# Actuator.net
KiCad netlist of a schematic drawn in Altium Designer
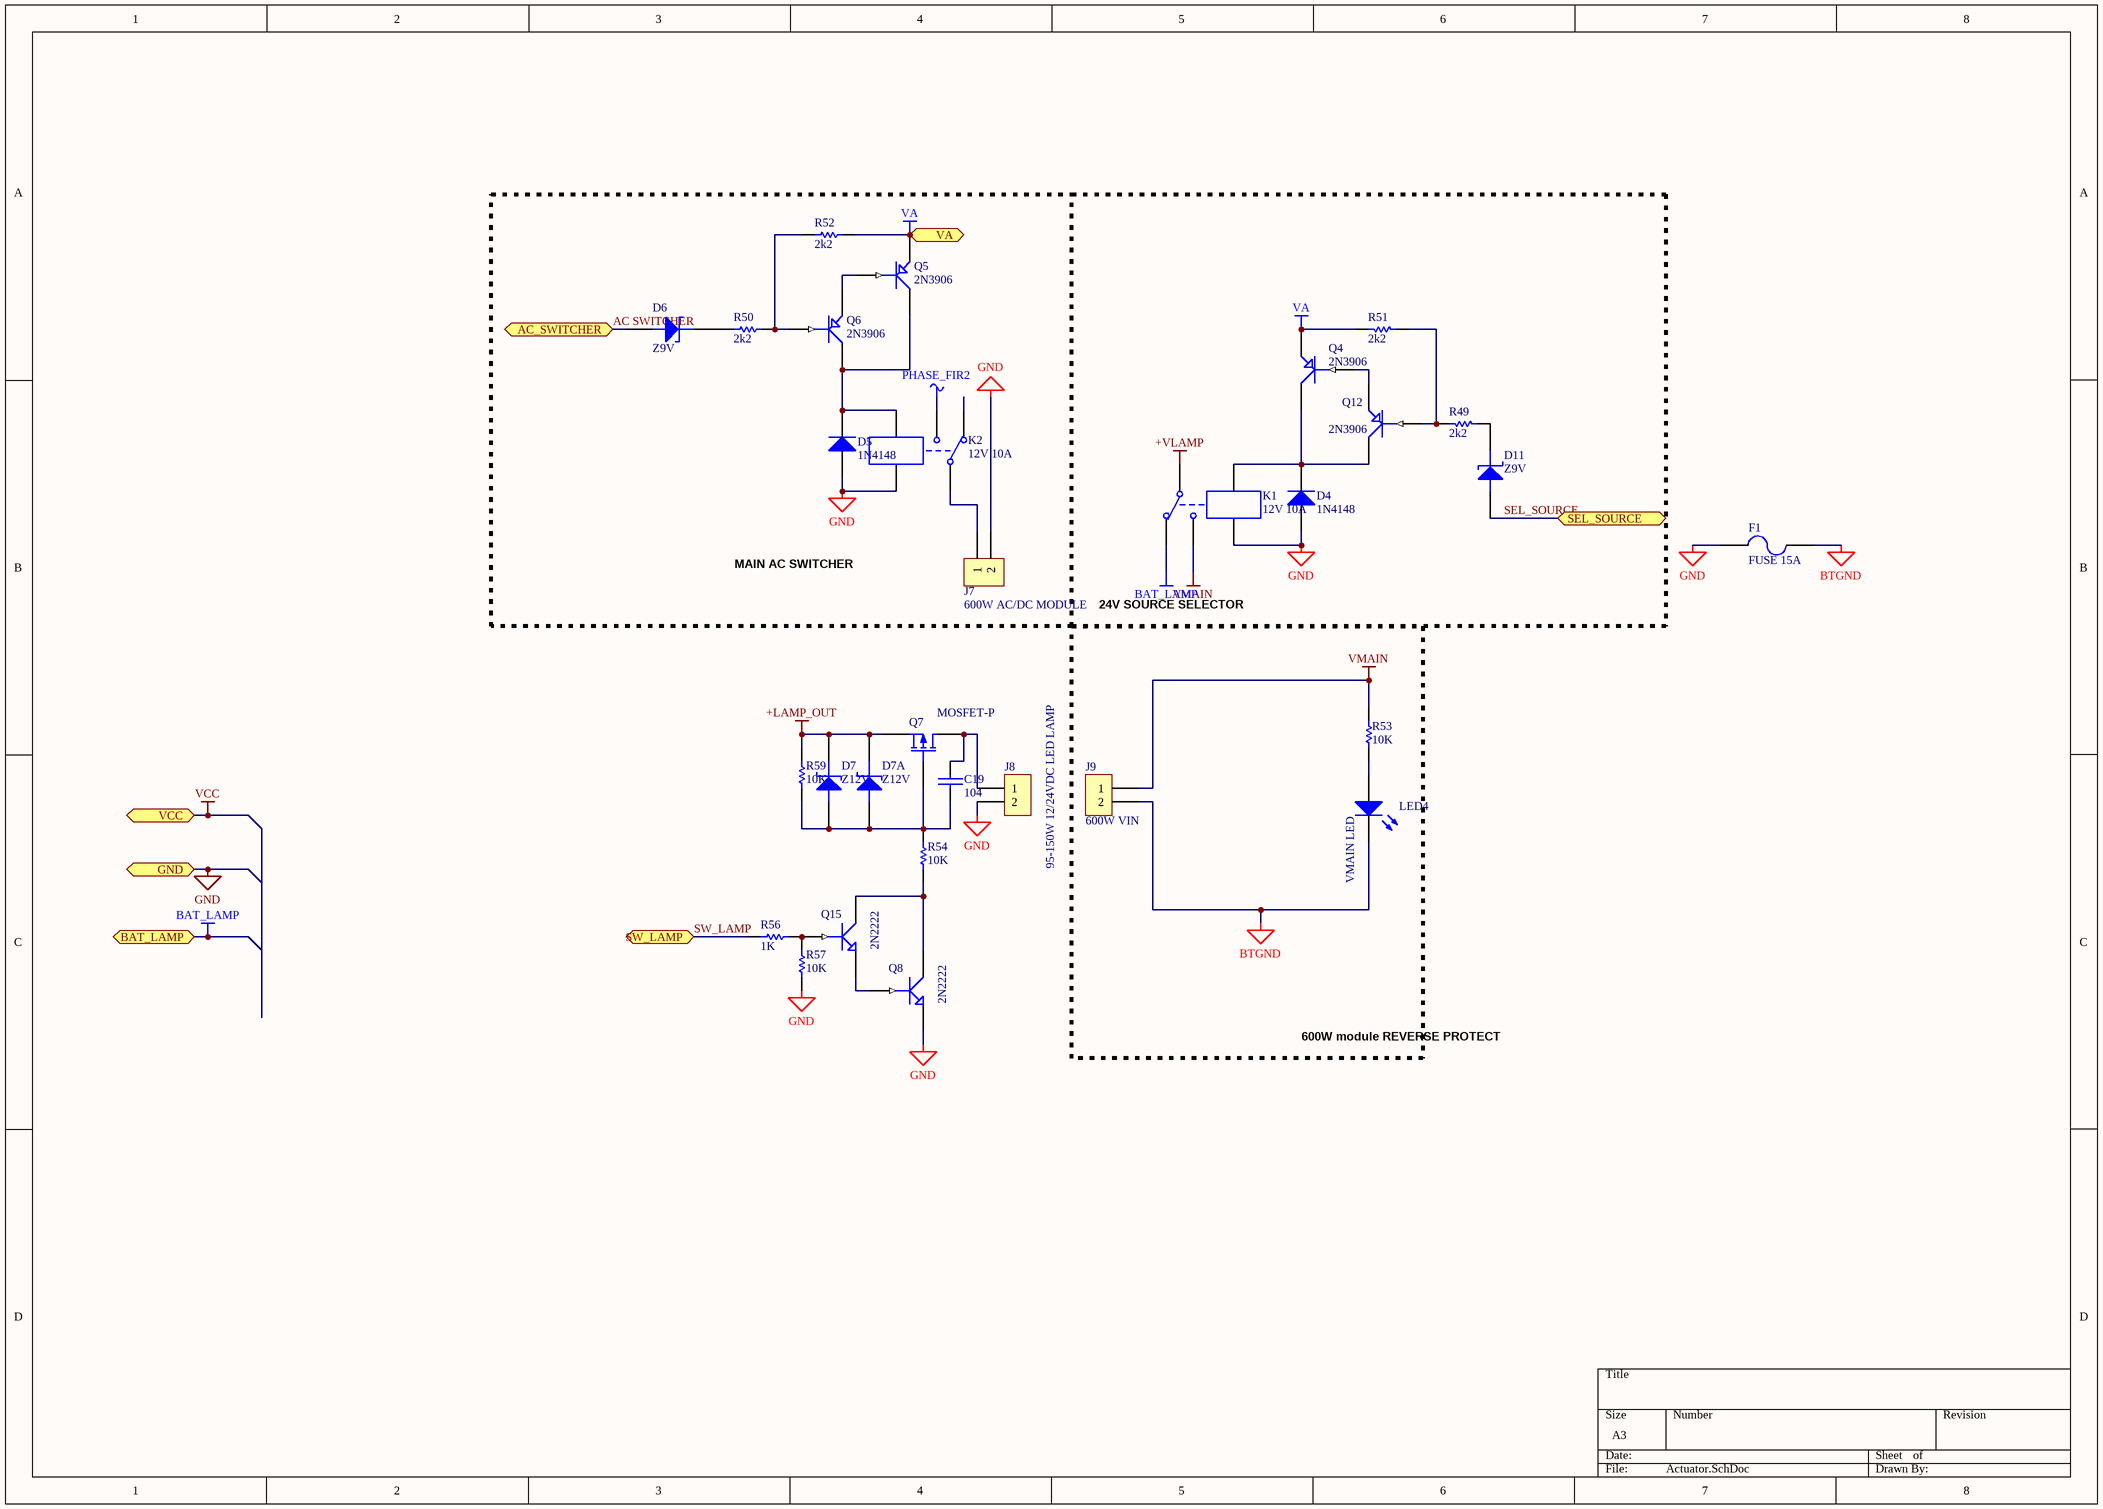
[diagram p0: Actuator.SchDoc]

(export (version "E")
  (design (tool "Eeschema 10.0.6"))
  (components
    (comp (ref "C19")
      (value "104")
      (footprint "C6-0805_N")
      (description "Capacitor")
      (libsource (lib "*") (part "CAP"))
    )
    (comp (ref "D4")
      (value "1N4148")
      (footprint "SOD80, LL-34")
      (description "1 Amp General Purpose Rectifier")
      (fields (field (name "PUBLISHER") "Altium Limited"))
      (libsource (lib "*") (part "Diode 1N4007"))
    )
    (comp (ref "D5")
      (value "1N4148")
      (footprint "SOD80, LL-34")
      (description "1 Amp General Purpose Rectifier")
      (fields (field (name "PUBLISHER") "Altium Limited"))
      (libsource (lib "*") (part "Diode 1N4007"))
    )
    (comp (ref "D6")
      (value "Z9V")
      (footprint "SOD80, LL-34")
      (description "Zener Diode")
      (libsource (lib "*") (part "ZENER2"))
    )
    (comp (ref "D7")
      (value "Z12V")
      (footprint "DO-35")
      (description "Zener Diode")
      (libsource (lib "*") (part "ZENER2"))
    )
    (comp (ref "D7A")
      (value "Z12V")
      (footprint "SOD80, LL-34")
      (description "Zener Diode")
      (libsource (lib "*") (part "ZENER2"))
    )
    (comp (ref "D11")
      (value "Z9V")
      (footprint "SOD80, LL-34")
      (description "Zener Diode")
      (libsource (lib "*") (part "ZENER2"))
    )
    (comp (ref "F1")
      (value "FUSE 15A")
      (footprint "FUSE2")
      (description "Fuse")
      (libsource (lib "*") (part "FUSE2"))
    )
    (comp (ref "J7")
      (value "600W AC/DC MODULE")
      (footprint "TERMINAL2")
      (description "Connector")
      (libsource (lib "") (part "CON2_2"))
    )
    (comp (ref "J8")
      (value "95-150W 12/24VDC LED LAMP")
      (footprint "TERMINAL2")
      (description "Connector")
      (libsource (lib "*") (part "CON2"))
    )
    (comp (ref "J9")
      (value "600W VIN")
      (footprint "TERMINAL2")
      (description "Connector")
      (libsource (lib "") (part "CON2_1"))
    )
    (comp (ref "K1")
      (value "12V 10A")
      (footprint "RELAYVUONG")
      (description "G5LA-10A/250VAC / SRC-12VDC-SL-C")
      (fields (field (name "PUBLISHER") "Altium Limited"))
      (libsource (lib "Miscellaneous Devices") (part "Relay-SPDT"))
    )
    (comp (ref "K2")
      (value "12V 10A")
      (footprint "RELAYVUONG")
      (description "G5LA-10A/250VAC / SRC-12VDC-SL-C")
      (fields (field (name "PUBLISHER") "Altium Limited"))
      (libsource (lib "Miscellaneous Devices") (part "Relay-SPDT"))
    )
    (comp (ref "LED4")
      (value "VMAIN LED")
      (footprint "led3mm")
      (description "Typical BLUE SiC LED")
      (fields (field (name "PUBLISHER") "Altium Limited"))
      (libsource (lib "Miscellaneous Devices") (part "LED3"))
    )
    (comp (ref "Q4")
      (value "2N3906")
      (footprint "SOT23-3")
      (description "PNP Transistor")
      (libsource (lib "*") (part "PNP1"))
    )
    (comp (ref "Q5")
      (value "2N3906")
      (footprint "SOT23-3")
      (description "PNP Transistor")
      (libsource (lib "*") (part "PNP1"))
    )
    (comp (ref "Q6")
      (value "2N3906")
      (footprint "SOT23-3")
      (description "PNP Transistor")
      (libsource (lib "*") (part "PNP1"))
    )
    (comp (ref "Q7")
      (value "MOSFET-P")
      (footprint "D2PAK-3")
      (description "P-Channel MOSFET")
      (fields (field (name "PUBLISHER") "Altium Limited"))
      (libsource (lib "Miscellaneous Devices") (part "MOSFET-P"))
    )
    (comp (ref "Q8")
      (value "2N2222")
      (footprint "SOT23-3")
      (description "NPN Transistor")
      (libsource (lib "*") (part "NPN1"))
    )
    (comp (ref "Q12")
      (value "2N3906")
      (footprint "SOT23-3")
      (description "PNP Transistor")
      (libsource (lib "*") (part "PNP1"))
    )
    (comp (ref "Q15")
      (value "2N2222")
      (footprint "SOT23-3")
      (description "NPN Transistor")
      (libsource (lib "*") (part "NPN1"))
    )
    (comp (ref "R49")
      (value "2k2")
      (footprint "6-0805_N")
      (description "Semiconductor Resistor")
      (fields (field (name "PUBLISHER") "Altium Limited"))
      (libsource (lib "*") (part "Res Semi"))
    )
    (comp (ref "R50")
      (value "2k2")
      (footprint "6-0805_N")
      (description "Semiconductor Resistor")
      (fields (field (name "PUBLISHER") "Altium Limited"))
      (libsource (lib "*") (part "Res Semi"))
    )
    (comp (ref "R51")
      (value "2k2")
      (footprint "6-0805_N")
      (description "Semiconductor Resistor")
      (fields (field (name "PUBLISHER") "Altium Limited"))
      (libsource (lib "*") (part "Res Semi"))
    )
    (comp (ref "R52")
      (value "2k2")
      (footprint "6-0805_N")
      (description "Semiconductor Resistor")
      (fields (field (name "PUBLISHER") "Altium Limited"))
      (libsource (lib "*") (part "Res Semi"))
    )
    (comp (ref "R53")
      (value "10K")
      (footprint "6-0805_N")
      (description "Semiconductor Resistor")
      (fields (field (name "PUBLISHER") "*"))
      (libsource (lib "*") (part "Res Semi"))
    )
    (comp (ref "R54")
      (value "10K")
      (footprint "6-0805_N")
      (description "Semiconductor Resistor")
      (fields (field (name "PUBLISHER") "Altium Limited"))
      (libsource (lib "*") (part "Res Semi"))
    )
    (comp (ref "R56")
      (value "1K")
      (footprint "6-0805_N")
      (description "Semiconductor Resistor")
      (fields (field (name "PUBLISHER") "Altium Limited"))
      (libsource (lib "*") (part "Res Semi"))
    )
    (comp (ref "R57")
      (value "10K")
      (footprint "6-0805_N")
      (description "Semiconductor Resistor")
      (fields (field (name "PUBLISHER") "Altium Limited"))
      (libsource (lib "*") (part "Res Semi"))
    )
    (comp (ref "R59")
      (value "10K")
      (footprint "6-0805_N")
      (description "Semiconductor Resistor")
      (fields (field (name "PUBLISHER") "Altium Limited"))
      (libsource (lib "*") (part "Res Semi"))
    )
  )
  (nets
    (net (code "1") (name "+LAMP_OUT") (class "Default")
      (node (ref "D7") (pin "2") (pinfunction "K_2") (pintype "passive"))
      (node (ref "D7A") (pin "2") (pinfunction "K_2") (pintype "passive"))
      (node (ref "Q7") (pin "3") (pinfunction "S_3") (pintype "passive"))
      (node (ref "R59") (pin "2") (pinfunction "2_2") (pintype "passive"))
    )
    (net (code "2") (name "+VLAMP") (class "Default")
      (node (ref "K1") (pin "1") (pinfunction "1_1") (pintype "passive"))
    )
    (net (code "3") (name "/AC SWITCHER") (class "Default")
      (node (ref "D6") (pin "1") (pinfunction "A_1") (pintype "passive"))
    )
    (net (code "4") (name "/SEL_SOURCE") (class "Default")
      (node (ref "D11") (pin "1") (pinfunction "A_1") (pintype "passive"))
    )
    (net (code "5") (name "/SW_LAMP") (class "Default")
      (node (ref "R56") (pin "1") (pinfunction "1_1") (pintype "passive"))
    )
    (net (code "6") (name "BAT_LAMP") (class "Default")
      (node (ref "K1") (pin "2") (pinfunction "2_2") (pintype "passive"))
    )
    (net (code "7") (name "BTGND") (class "Default")
      (node (ref "F1") (pin "2") (pinfunction "2_2") (pintype "passive"))
      (node (ref "J9") (pin "2") (pinfunction "2_2") (pintype "passive"))
      (node (ref "LED4") (pin "2") (pinfunction "K_2") (pintype "passive"))
    )
    (net (code "8") (name "GND") (class "Default")
      (node (ref "D4") (pin "1") (pinfunction "A_1") (pintype "passive"))
      (node (ref "D5") (pin "1") (pinfunction "A_1") (pintype "passive"))
      (node (ref "F1") (pin "1") (pinfunction "1_1") (pintype "passive"))
      (node (ref "J7") (pin "2") (pinfunction "2_2") (pintype "passive"))
      (node (ref "J8") (pin "2") (pinfunction "2_2") (pintype "passive"))
      (node (ref "K1") (pin "5") (pinfunction "5_5") (pintype "passive"))
      (node (ref "K2") (pin "4") (pinfunction "4_4") (pintype "passive"))
      (node (ref "Q8") (pin "2") (pinfunction "E_2") (pintype "passive"))
      (node (ref "R57") (pin "1") (pinfunction "1_1") (pintype "passive"))
    )
    (net (code "9") (name "Net-(D4-K)") (class "Default")
      (node (ref "D4") (pin "2") (pinfunction "K_2") (pintype "passive"))
      (node (ref "K1") (pin "4") (pinfunction "4_4") (pintype "passive"))
      (node (ref "Q12") (pin "3") (pinfunction "C_3") (pintype "passive"))
      (node (ref "Q4") (pin "3") (pinfunction "C_3") (pintype "passive"))
    )
    (net (code "10") (name "Net-(D5-K)") (class "Default")
      (node (ref "D5") (pin "2") (pinfunction "K_2") (pintype "passive"))
      (node (ref "K2") (pin "5") (pinfunction "5_5") (pintype "passive"))
      (node (ref "Q5") (pin "3") (pinfunction "C_3") (pintype "passive"))
      (node (ref "Q6") (pin "3") (pinfunction "C_3") (pintype "passive"))
    )
    (net (code "11") (name "Net-(D6-K)") (class "Default")
      (node (ref "D6") (pin "2") (pinfunction "K_2") (pintype "passive"))
      (node (ref "R50") (pin "1") (pinfunction "1_1") (pintype "passive"))
    )
    (net (code "12") (name "Net-(D7-A)") (class "Default")
      (node (ref "C19") (pin "2") (pinfunction "2_2") (pintype "passive"))
      (node (ref "D7") (pin "1") (pinfunction "A_1") (pintype "passive"))
      (node (ref "D7A") (pin "1") (pinfunction "A_1") (pintype "passive"))
      (node (ref "Q7") (pin "1") (pinfunction "G_1") (pintype "passive"))
      (node (ref "R54") (pin "2") (pinfunction "2_2") (pintype "passive"))
      (node (ref "R59") (pin "1") (pinfunction "1_1") (pintype "passive"))
    )
    (net (code "13") (name "Net-(D11-K)") (class "Default")
      (node (ref "D11") (pin "2") (pinfunction "K_2") (pintype "passive"))
      (node (ref "R49") (pin "1") (pinfunction "1_1") (pintype "passive"))
    )
    (net (code "14") (name "Net-(J7-Pad1)") (class "Default")
      (node (ref "J7") (pin "1") (pinfunction "1_1") (pintype "passive"))
      (node (ref "K2") (pin "1") (pinfunction "1_1") (pintype "passive"))
    )
    (net (code "15") (name "Net-(LED4-A)") (class "Default")
      (node (ref "LED4") (pin "1") (pinfunction "A_1") (pintype "passive"))
      (node (ref "R53") (pin "1") (pinfunction "1_1") (pintype "passive"))
    )
    (net (code "16") (name "Net-(Q5-B)") (class "Default")
      (node (ref "Q5") (pin "1") (pinfunction "B_1") (pintype "input"))
      (node (ref "Q6") (pin "2") (pinfunction "E_2") (pintype "passive"))
    )
    (net (code "17") (name "Net-(Q6-B)") (class "Default")
      (node (ref "Q6") (pin "1") (pinfunction "B_1") (pintype "input"))
      (node (ref "R50") (pin "2") (pinfunction "2_2") (pintype "passive"))
      (node (ref "R52") (pin "1") (pinfunction "1_1") (pintype "passive"))
    )
    (net (code "18") (name "Net-(Q7-D)") (class "Default")
      (node (ref "C19") (pin "1") (pinfunction "1_1") (pintype "passive"))
      (node (ref "J8") (pin "1") (pinfunction "1_1") (pintype "passive"))
      (node (ref "Q7") (pin "2") (pinfunction "D_2") (pintype "passive"))
    )
    (net (code "19") (name "Net-(Q12-B)") (class "Default")
      (node (ref "Q12") (pin "1") (pinfunction "B_1") (pintype "input"))
      (node (ref "R49") (pin "2") (pinfunction "2_2") (pintype "passive"))
      (node (ref "R51") (pin "1") (pinfunction "1_1") (pintype "passive"))
    )
    (net (code "20") (name "Net-(Q12-E)") (class "Default")
      (node (ref "Q12") (pin "2") (pinfunction "E_2") (pintype "passive"))
      (node (ref "Q4") (pin "1") (pinfunction "B_1") (pintype "input"))
    )
    (net (code "21") (name "Net-(Q15-B)") (class "Default")
      (node (ref "Q15") (pin "1") (pinfunction "B_1") (pintype "input"))
      (node (ref "R56") (pin "2") (pinfunction "2_2") (pintype "passive"))
      (node (ref "R57") (pin "2") (pinfunction "2_2") (pintype "passive"))
    )
    (net (code "22") (name "Net-(Q15-C)") (class "Default")
      (node (ref "Q15") (pin "3") (pinfunction "C_3") (pintype "passive"))
      (node (ref "Q8") (pin "3") (pinfunction "C_3") (pintype "passive"))
      (node (ref "R54") (pin "1") (pinfunction "1_1") (pintype "passive"))
    )
    (net (code "23") (name "Net-(Q15-E)") (class "Default")
      (node (ref "Q15") (pin "2") (pinfunction "E_2") (pintype "passive"))
      (node (ref "Q8") (pin "1") (pinfunction "B_1") (pintype "input"))
    )
    (net (code "24") (name "PHASE_FIR2") (class "Default")
      (node (ref "K2") (pin "3") (pinfunction "3_3") (pintype "passive"))
    )
    (net (code "25") (name "VA") (class "Default")
      (node (ref "Q4") (pin "2") (pinfunction "E_2") (pintype "passive"))
      (node (ref "Q5") (pin "2") (pinfunction "E_2") (pintype "passive"))
      (node (ref "R51") (pin "2") (pinfunction "2_2") (pintype "passive"))
      (node (ref "R52") (pin "2") (pinfunction "2_2") (pintype "passive"))
    )
    (net (code "27") (name "VMAIN") (class "Default")
      (node (ref "J9") (pin "1") (pinfunction "1_1") (pintype "passive"))
      (node (ref "K1") (pin "3") (pinfunction "3_3") (pintype "passive"))
      (node (ref "R53") (pin "2") (pinfunction "2_2") (pintype "passive"))
    )
    (net (code "28") (name "unconnected-(K2-Pad2)") (class "Default")
      (node (ref "K2") (pin "2") (pinfunction "2_2") (pintype "passive"))
    )
  )
)
